# Sheet1.net
KiCad netlist of a schematic drawn in Altium Designer
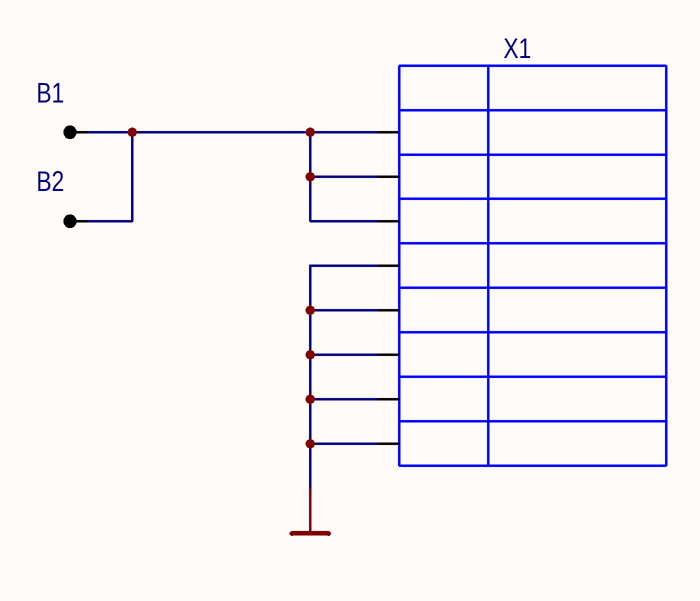
[diagram p0: Sheet1.SchDoc]

(export (version "E")
  (design (tool "Eeschema 10.0.6"))
  (components
    (comp (ref "B1") (value "Pin_1") (footprint "18650pad") (libsource (lib "Common_lib") (part "Pin_1")))
    (comp (ref "B2") (value "Pin_1") (footprint "18650pad") (libsource (lib "Common_lib") (part "Pin_1")))
    (comp (ref "X1")
      (value "PLS8")
      (footprint "FFC-SMD_6P-P0.50_FFC05001-06SBA124W5M")
      (fields (field (name "MANUFACTURER") "ф. Ningbo Zhenqin Electronic"))
      (libsource (lib "Common_lib") (part "PLS8"))
    )
  )
  (nets
    (net (code "1") (name "GND") (class "Default")
      (node (ref "X1") (pin "4") (pintype "passive"))
      (node (ref "X1") (pin "5") (pintype "passive"))
      (node (ref "X1") (pin "6") (pintype "passive"))
      (node (ref "X1") (pin "7") (pintype "passive"))
      (node (ref "X1") (pin "8") (pintype "passive"))
    )
    (net (code "2") (name "Net-(B1-Pad1)") (class "Default")
      (node (ref "B1") (pin "1") (pintype "passive"))
      (node (ref "B2") (pin "1") (pintype "passive"))
      (node (ref "X1") (pin "1") (pintype "passive"))
      (node (ref "X1") (pin "2") (pintype "passive"))
      (node (ref "X1") (pin "3") (pintype "passive"))
    )
  )
)
